# ODU_Display_Line_0603.net
KiCad netlist of a schematic drawn in EAGLE
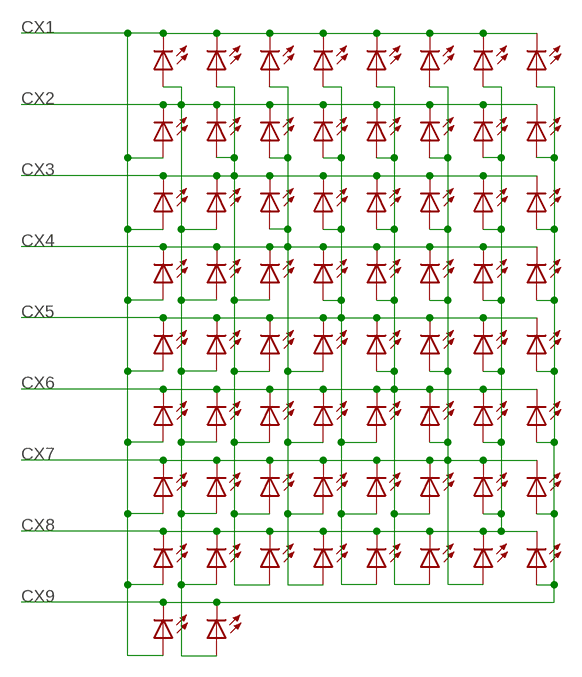
[diagram p0: schematic, sheet 1]

(export (version "E")
  (design (tool "Eeschema 10.0.6"))
  (components
    (comp (ref "LED_A1")
      (value "LEDSMT0603_1")
      (footprint "eagle-import:CHIPLED_0603")
      (libsource (lib "eagle-import") (part "LED0603_1SMT"))
    )
    (comp (ref "LED_A2")
      (value "LEDSMT0603_1")
      (footprint "eagle-import:CHIPLED_0603")
      (libsource (lib "eagle-import") (part "LED0603_1SMT"))
    )
    (comp (ref "LED_A3")
      (value "LEDSMT0603_1")
      (footprint "eagle-import:CHIPLED_0603")
      (libsource (lib "eagle-import") (part "LED0603_1SMT"))
    )
    (comp (ref "LED_A4")
      (value "LEDSMT0603_1")
      (footprint "eagle-import:CHIPLED_0603")
      (libsource (lib "eagle-import") (part "LED0603_1SMT"))
    )
    (comp (ref "LED_B1")
      (value "LEDSMT0603_1")
      (footprint "eagle-import:CHIPLED_0603")
      (libsource (lib "eagle-import") (part "LED0603_1SMT"))
    )
    (comp (ref "LED_B2")
      (value "LEDSMT0603_1")
      (footprint "eagle-import:CHIPLED_0603")
      (libsource (lib "eagle-import") (part "LED0603_1SMT"))
    )
    (comp (ref "LED_B3")
      (value "LEDSMT0603_1")
      (footprint "eagle-import:CHIPLED_0603")
      (libsource (lib "eagle-import") (part "LED0603_1SMT"))
    )
    (comp (ref "LED_B4")
      (value "LEDSMT0603_1")
      (footprint "eagle-import:CHIPLED_0603")
      (libsource (lib "eagle-import") (part "LED0603_1SMT"))
    )
    (comp (ref "LED_C1")
      (value "LEDSMT0603_1")
      (footprint "eagle-import:CHIPLED_0603")
      (libsource (lib "eagle-import") (part "LED0603_1SMT"))
    )
    (comp (ref "LED_C2")
      (value "LEDSMT0603_1")
      (footprint "eagle-import:CHIPLED_0603")
      (libsource (lib "eagle-import") (part "LED0603_1SMT"))
    )
    (comp (ref "LED_C3")
      (value "LEDSMT0603_1")
      (footprint "eagle-import:CHIPLED_0603")
      (libsource (lib "eagle-import") (part "LED0603_1SMT"))
    )
    (comp (ref "LED_C4")
      (value "LEDSMT0603_1")
      (footprint "eagle-import:CHIPLED_0603")
      (libsource (lib "eagle-import") (part "LED0603_1SMT"))
    )
    (comp (ref "LED_D1")
      (value "LEDSMT0603_1")
      (footprint "eagle-import:CHIPLED_0603")
      (libsource (lib "eagle-import") (part "LED0603_1SMT"))
    )
    (comp (ref "LED_D2")
      (value "LEDSMT0603_1")
      (footprint "eagle-import:CHIPLED_0603")
      (libsource (lib "eagle-import") (part "LED0603_1SMT"))
    )
    (comp (ref "LED_D3")
      (value "LEDSMT0603_1")
      (footprint "eagle-import:CHIPLED_0603")
      (libsource (lib "eagle-import") (part "LED0603_1SMT"))
    )
    (comp (ref "LED_D4")
      (value "LEDSMT0603_1")
      (footprint "eagle-import:CHIPLED_0603")
      (libsource (lib "eagle-import") (part "LED0603_1SMT"))
    )
    (comp (ref "LED_E1")
      (value "LEDSMT0603_1")
      (footprint "eagle-import:CHIPLED_0603")
      (libsource (lib "eagle-import") (part "LED0603_1SMT"))
    )
    (comp (ref "LED_E2")
      (value "LEDSMT0603_1")
      (footprint "eagle-import:CHIPLED_0603")
      (libsource (lib "eagle-import") (part "LED0603_1SMT"))
    )
    (comp (ref "LED_E3")
      (value "LEDSMT0603_1")
      (footprint "eagle-import:CHIPLED_0603")
      (libsource (lib "eagle-import") (part "LED0603_1SMT"))
    )
    (comp (ref "LED_E4")
      (value "LEDSMT0603_1")
      (footprint "eagle-import:CHIPLED_0603")
      (libsource (lib "eagle-import") (part "LED0603_1SMT"))
    )
    (comp (ref "LED_F1")
      (value "LEDSMT0603_1")
      (footprint "eagle-import:CHIPLED_0603")
      (libsource (lib "eagle-import") (part "LED0603_1SMT"))
    )
    (comp (ref "LED_F2")
      (value "LEDSMT0603_1")
      (footprint "eagle-import:CHIPLED_0603")
      (libsource (lib "eagle-import") (part "LED0603_1SMT"))
    )
    (comp (ref "LED_F3")
      (value "LEDSMT0603_1")
      (footprint "eagle-import:CHIPLED_0603")
      (libsource (lib "eagle-import") (part "LED0603_1SMT"))
    )
    (comp (ref "LED_F4")
      (value "LEDSMT0603_1")
      (footprint "eagle-import:CHIPLED_0603")
      (libsource (lib "eagle-import") (part "LED0603_1SMT"))
    )
    (comp (ref "LED_G1")
      (value "LEDSMT0603_1")
      (footprint "eagle-import:CHIPLED_0603")
      (libsource (lib "eagle-import") (part "LED0603_1SMT"))
    )
    (comp (ref "LED_G2")
      (value "LEDSMT0603_1")
      (footprint "eagle-import:CHIPLED_0603")
      (libsource (lib "eagle-import") (part "LED0603_1SMT"))
    )
    (comp (ref "LED_G3")
      (value "LEDSMT0603_1")
      (footprint "eagle-import:CHIPLED_0603")
      (libsource (lib "eagle-import") (part "LED0603_1SMT"))
    )
    (comp (ref "LED_G4")
      (value "LEDSMT0603_1")
      (footprint "eagle-import:CHIPLED_0603")
      (libsource (lib "eagle-import") (part "LED0603_1SMT"))
    )
    (comp (ref "LED_H1")
      (value "LEDSMT0603_1")
      (footprint "eagle-import:CHIPLED_0603")
      (libsource (lib "eagle-import") (part "LED0603_1SMT"))
    )
    (comp (ref "LED_H2")
      (value "LEDSMT0603_1")
      (footprint "eagle-import:CHIPLED_0603")
      (libsource (lib "eagle-import") (part "LED0603_1SMT"))
    )
    (comp (ref "LED_H3")
      (value "LEDSMT0603_1")
      (footprint "eagle-import:CHIPLED_0603")
      (libsource (lib "eagle-import") (part "LED0603_1SMT"))
    )
    (comp (ref "LED_H4")
      (value "LEDSMT0603_1")
      (footprint "eagle-import:CHIPLED_0603")
      (libsource (lib "eagle-import") (part "LED0603_1SMT"))
    )
    (comp (ref "LED_K1")
      (value "LEDSMT0603_1")
      (footprint "eagle-import:CHIPLED_0603")
      (libsource (lib "eagle-import") (part "LED0603_1SMT"))
    )
    (comp (ref "LED_K2")
      (value "LEDSMT0603_1")
      (footprint "eagle-import:CHIPLED_0603")
      (libsource (lib "eagle-import") (part "LED0603_1SMT"))
    )
    (comp (ref "LED_K3")
      (value "LEDSMT0603_1")
      (footprint "eagle-import:CHIPLED_0603")
      (libsource (lib "eagle-import") (part "LED0603_1SMT"))
    )
    (comp (ref "LED_K4")
      (value "LEDSMT0603_1")
      (footprint "eagle-import:CHIPLED_0603")
      (libsource (lib "eagle-import") (part "LED0603_1SMT"))
    )
    (comp (ref "LED_M1")
      (value "LEDSMT0603_1")
      (footprint "eagle-import:CHIPLED_0603")
      (libsource (lib "eagle-import") (part "LED0603_1SMT"))
    )
    (comp (ref "LED_M2")
      (value "LEDSMT0603_1")
      (footprint "eagle-import:CHIPLED_0603")
      (libsource (lib "eagle-import") (part "LED0603_1SMT"))
    )
    (comp (ref "LED_M3")
      (value "LEDSMT0603_1")
      (footprint "eagle-import:CHIPLED_0603")
      (libsource (lib "eagle-import") (part "LED0603_1SMT"))
    )
    (comp (ref "LED_M4")
      (value "LEDSMT0603_1")
      (footprint "eagle-import:CHIPLED_0603")
      (libsource (lib "eagle-import") (part "LED0603_1SMT"))
    )
    (comp (ref "LED_N1")
      (value "LEDSMT0603_1")
      (footprint "eagle-import:CHIPLED_0603")
      (libsource (lib "eagle-import") (part "LED0603_1SMT"))
    )
    (comp (ref "LED_N2")
      (value "LEDSMT0603_1")
      (footprint "eagle-import:CHIPLED_0603")
      (libsource (lib "eagle-import") (part "LED0603_1SMT"))
    )
    (comp (ref "LED_N3")
      (value "LEDSMT0603_1")
      (footprint "eagle-import:CHIPLED_0603")
      (libsource (lib "eagle-import") (part "LED0603_1SMT"))
    )
    (comp (ref "LED_N4")
      (value "LEDSMT0603_1")
      (footprint "eagle-import:CHIPLED_0603")
      (libsource (lib "eagle-import") (part "LED0603_1SMT"))
    )
    (comp (ref "LED_P1")
      (value "LEDSMT0603_1")
      (footprint "eagle-import:CHIPLED_0603")
      (libsource (lib "eagle-import") (part "LED0603_1SMT"))
    )
    (comp (ref "LED_P2")
      (value "LEDSMT0603_1")
      (footprint "eagle-import:CHIPLED_0603")
      (libsource (lib "eagle-import") (part "LED0603_1SMT"))
    )
    (comp (ref "LED_P3")
      (value "LEDSMT0603_1")
      (footprint "eagle-import:CHIPLED_0603")
      (libsource (lib "eagle-import") (part "LED0603_1SMT"))
    )
    (comp (ref "LED_P4")
      (value "LEDSMT0603_1")
      (footprint "eagle-import:CHIPLED_0603")
      (libsource (lib "eagle-import") (part "LED0603_1SMT"))
    )
    (comp (ref "LED_R1")
      (value "LEDSMT0603_1")
      (footprint "eagle-import:CHIPLED_0603")
      (libsource (lib "eagle-import") (part "LED0603_1SMT"))
    )
    (comp (ref "LED_R2")
      (value "LEDSMT0603_1")
      (footprint "eagle-import:CHIPLED_0603")
      (libsource (lib "eagle-import") (part "LED0603_1SMT"))
    )
    (comp (ref "LED_R3")
      (value "LEDSMT0603_1")
      (footprint "eagle-import:CHIPLED_0603")
      (libsource (lib "eagle-import") (part "LED0603_1SMT"))
    )
    (comp (ref "LED_R4")
      (value "LEDSMT0603_1")
      (footprint "eagle-import:CHIPLED_0603")
      (libsource (lib "eagle-import") (part "LED0603_1SMT"))
    )
    (comp (ref "LED_S1")
      (value "LEDSMT0603_1")
      (footprint "eagle-import:CHIPLED_0603")
      (libsource (lib "eagle-import") (part "LED0603_1SMT"))
    )
    (comp (ref "LED_S2")
      (value "LEDSMT0603_1")
      (footprint "eagle-import:CHIPLED_0603")
      (libsource (lib "eagle-import") (part "LED0603_1SMT"))
    )
    (comp (ref "LED_S3")
      (value "LEDSMT0603_1")
      (footprint "eagle-import:CHIPLED_0603")
      (libsource (lib "eagle-import") (part "LED0603_1SMT"))
    )
    (comp (ref "LED_S4")
      (value "LEDSMT0603_1")
      (footprint "eagle-import:CHIPLED_0603")
      (libsource (lib "eagle-import") (part "LED0603_1SMT"))
    )
    (comp (ref "LED_SEL1")
      (value "LEDSMT0603_1")
      (footprint "eagle-import:CHIPLED_0603")
      (libsource (lib "eagle-import") (part "LED0603_1SMT"))
    )
    (comp (ref "LED_SEL2")
      (value "LEDSMT0603_1")
      (footprint "eagle-import:CHIPLED_0603")
      (libsource (lib "eagle-import") (part "LED0603_1SMT"))
    )
    (comp (ref "LED_T1")
      (value "LEDSMT0603_1")
      (footprint "eagle-import:CHIPLED_0603")
      (libsource (lib "eagle-import") (part "LED0603_1SMT"))
    )
    (comp (ref "LED_T2")
      (value "LEDSMT0603_1")
      (footprint "eagle-import:CHIPLED_0603")
      (libsource (lib "eagle-import") (part "LED0603_1SMT"))
    )
    (comp (ref "LED_T3")
      (value "LEDSMT0603_1")
      (footprint "eagle-import:CHIPLED_0603")
      (libsource (lib "eagle-import") (part "LED0603_1SMT"))
    )
    (comp (ref "LED_T4")
      (value "LEDSMT0603_1")
      (footprint "eagle-import:CHIPLED_0603")
      (libsource (lib "eagle-import") (part "LED0603_1SMT"))
    )
    (comp (ref "LED_U1")
      (value "LEDSMT0603_1")
      (footprint "eagle-import:CHIPLED_0603")
      (libsource (lib "eagle-import") (part "LED0603_1SMT"))
    )
    (comp (ref "LED_U2")
      (value "LEDSMT0603_1")
      (footprint "eagle-import:CHIPLED_0603")
      (libsource (lib "eagle-import") (part "LED0603_1SMT"))
    )
    (comp (ref "LED_U3")
      (value "LEDSMT0603_1")
      (footprint "eagle-import:CHIPLED_0603")
      (libsource (lib "eagle-import") (part "LED0603_1SMT"))
    )
    (comp (ref "LED_U4")
      (value "LEDSMT0603_1")
      (footprint "eagle-import:CHIPLED_0603")
      (libsource (lib "eagle-import") (part "LED0603_1SMT"))
    )
  )
  (nets
    (net (code "1") (name "/CX1") (class "Default")
      (node (ref "LED_A1") (pin "C") (pinfunction "C_C") (pintype "passive"))
      (node (ref "LED_A2") (pin "A") (pinfunction "A_A") (pintype "passive"))
      (node (ref "LED_A3") (pin "A") (pinfunction "A_A") (pintype "passive"))
      (node (ref "LED_A4") (pin "A") (pinfunction "A_A") (pintype "passive"))
      (node (ref "LED_B1") (pin "C") (pinfunction "C_C") (pintype "passive"))
      (node (ref "LED_C1") (pin "C") (pinfunction "C_C") (pintype "passive"))
      (node (ref "LED_D1") (pin "C") (pinfunction "C_C") (pintype "passive"))
      (node (ref "LED_E1") (pin "C") (pinfunction "C_C") (pintype "passive"))
      (node (ref "LED_F1") (pin "C") (pinfunction "C_C") (pintype "passive"))
      (node (ref "LED_G1") (pin "C") (pinfunction "C_C") (pintype "passive"))
      (node (ref "LED_H1") (pin "C") (pinfunction "C_C") (pintype "passive"))
      (node (ref "LED_K1") (pin "A") (pinfunction "A_A") (pintype "passive"))
      (node (ref "LED_K2") (pin "A") (pinfunction "A_A") (pintype "passive"))
      (node (ref "LED_K3") (pin "A") (pinfunction "A_A") (pintype "passive"))
      (node (ref "LED_K4") (pin "A") (pinfunction "A_A") (pintype "passive"))
      (node (ref "LED_SEL1") (pin "A") (pinfunction "A_A") (pintype "passive"))
    )
    (net (code "2") (name "/CX2") (class "Default")
      (node (ref "LED_A1") (pin "A") (pinfunction "A_A") (pintype "passive"))
      (node (ref "LED_B2") (pin "A") (pinfunction "A_A") (pintype "passive"))
      (node (ref "LED_B3") (pin "A") (pinfunction "A_A") (pintype "passive"))
      (node (ref "LED_B4") (pin "A") (pinfunction "A_A") (pintype "passive"))
      (node (ref "LED_K1") (pin "C") (pinfunction "C_C") (pintype "passive"))
      (node (ref "LED_M1") (pin "C") (pinfunction "C_C") (pintype "passive"))
      (node (ref "LED_M2") (pin "A") (pinfunction "A_A") (pintype "passive"))
      (node (ref "LED_M3") (pin "A") (pinfunction "A_A") (pintype "passive"))
      (node (ref "LED_M4") (pin "A") (pinfunction "A_A") (pintype "passive"))
      (node (ref "LED_N1") (pin "C") (pinfunction "C_C") (pintype "passive"))
      (node (ref "LED_P1") (pin "C") (pinfunction "C_C") (pintype "passive"))
      (node (ref "LED_R1") (pin "C") (pinfunction "C_C") (pintype "passive"))
      (node (ref "LED_S1") (pin "C") (pinfunction "C_C") (pintype "passive"))
      (node (ref "LED_SEL2") (pin "A") (pinfunction "A_A") (pintype "passive"))
      (node (ref "LED_T1") (pin "C") (pinfunction "C_C") (pintype "passive"))
      (node (ref "LED_U1") (pin "C") (pinfunction "C_C") (pintype "passive"))
    )
    (net (code "3") (name "/CX3") (class "Default")
      (node (ref "LED_A2") (pin "C") (pinfunction "C_C") (pintype "passive"))
      (node (ref "LED_B1") (pin "A") (pinfunction "A_A") (pintype "passive"))
      (node (ref "LED_B2") (pin "C") (pinfunction "C_C") (pintype "passive"))
      (node (ref "LED_C2") (pin "C") (pinfunction "C_C") (pintype "passive"))
      (node (ref "LED_C3") (pin "A") (pinfunction "A_A") (pintype "passive"))
      (node (ref "LED_C4") (pin "A") (pinfunction "A_A") (pintype "passive"))
      (node (ref "LED_D2") (pin "C") (pinfunction "C_C") (pintype "passive"))
      (node (ref "LED_E2") (pin "C") (pinfunction "C_C") (pintype "passive"))
      (node (ref "LED_F2") (pin "C") (pinfunction "C_C") (pintype "passive"))
      (node (ref "LED_G2") (pin "C") (pinfunction "C_C") (pintype "passive"))
      (node (ref "LED_H2") (pin "C") (pinfunction "C_C") (pintype "passive"))
      (node (ref "LED_M1") (pin "A") (pinfunction "A_A") (pintype "passive"))
      (node (ref "LED_N2") (pin "A") (pinfunction "A_A") (pintype "passive"))
      (node (ref "LED_N3") (pin "A") (pinfunction "A_A") (pintype "passive"))
      (node (ref "LED_N4") (pin "A") (pinfunction "A_A") (pintype "passive"))
    )
    (net (code "4") (name "/CX4") (class "Default")
      (node (ref "LED_C1") (pin "A") (pinfunction "A_A") (pintype "passive"))
      (node (ref "LED_C2") (pin "A") (pinfunction "A_A") (pintype "passive"))
      (node (ref "LED_D3") (pin "A") (pinfunction "A_A") (pintype "passive"))
      (node (ref "LED_D4") (pin "A") (pinfunction "A_A") (pintype "passive"))
      (node (ref "LED_K2") (pin "C") (pinfunction "C_C") (pintype "passive"))
      (node (ref "LED_M2") (pin "C") (pinfunction "C_C") (pintype "passive"))
      (node (ref "LED_N1") (pin "A") (pinfunction "A_A") (pintype "passive"))
      (node (ref "LED_N2") (pin "C") (pinfunction "C_C") (pintype "passive"))
      (node (ref "LED_P2") (pin "C") (pinfunction "C_C") (pintype "passive"))
      (node (ref "LED_P3") (pin "A") (pinfunction "A_A") (pintype "passive"))
      (node (ref "LED_P4") (pin "A") (pinfunction "A_A") (pintype "passive"))
      (node (ref "LED_R2") (pin "C") (pinfunction "C_C") (pintype "passive"))
      (node (ref "LED_S2") (pin "C") (pinfunction "C_C") (pintype "passive"))
      (node (ref "LED_T2") (pin "C") (pinfunction "C_C") (pintype "passive"))
      (node (ref "LED_U2") (pin "C") (pinfunction "C_C") (pintype "passive"))
    )
    (net (code "5") (name "/CX5") (class "Default")
      (node (ref "LED_A3") (pin "C") (pinfunction "C_C") (pintype "passive"))
      (node (ref "LED_B3") (pin "C") (pinfunction "C_C") (pintype "passive"))
      (node (ref "LED_C3") (pin "C") (pinfunction "C_C") (pintype "passive"))
      (node (ref "LED_D1") (pin "A") (pinfunction "A_A") (pintype "passive"))
      (node (ref "LED_D2") (pin "A") (pinfunction "A_A") (pintype "passive"))
      (node (ref "LED_D3") (pin "C") (pinfunction "C_C") (pintype "passive"))
      (node (ref "LED_E3") (pin "C") (pinfunction "C_C") (pintype "passive"))
      (node (ref "LED_E4") (pin "A") (pinfunction "A_A") (pintype "passive"))
      (node (ref "LED_F3") (pin "C") (pinfunction "C_C") (pintype "passive"))
      (node (ref "LED_G3") (pin "C") (pinfunction "C_C") (pintype "passive"))
      (node (ref "LED_H3") (pin "C") (pinfunction "C_C") (pintype "passive"))
      (node (ref "LED_P1") (pin "A") (pinfunction "A_A") (pintype "passive"))
      (node (ref "LED_P2") (pin "A") (pinfunction "A_A") (pintype "passive"))
      (node (ref "LED_R3") (pin "A") (pinfunction "A_A") (pintype "passive"))
      (node (ref "LED_R4") (pin "A") (pinfunction "A_A") (pintype "passive"))
    )
    (net (code "6") (name "/CX6") (class "Default")
      (node (ref "LED_E1") (pin "A") (pinfunction "A_A") (pintype "passive"))
      (node (ref "LED_E2") (pin "A") (pinfunction "A_A") (pintype "passive"))
      (node (ref "LED_E3") (pin "A") (pinfunction "A_A") (pintype "passive"))
      (node (ref "LED_F4") (pin "A") (pinfunction "A_A") (pintype "passive"))
      (node (ref "LED_K3") (pin "C") (pinfunction "C_C") (pintype "passive"))
      (node (ref "LED_M3") (pin "C") (pinfunction "C_C") (pintype "passive"))
      (node (ref "LED_N3") (pin "C") (pinfunction "C_C") (pintype "passive"))
      (node (ref "LED_P3") (pin "C") (pinfunction "C_C") (pintype "passive"))
      (node (ref "LED_R1") (pin "A") (pinfunction "A_A") (pintype "passive"))
      (node (ref "LED_R2") (pin "A") (pinfunction "A_A") (pintype "passive"))
      (node (ref "LED_R3") (pin "C") (pinfunction "C_C") (pintype "passive"))
      (node (ref "LED_S3") (pin "C") (pinfunction "C_C") (pintype "passive"))
      (node (ref "LED_S4") (pin "A") (pinfunction "A_A") (pintype "passive"))
      (node (ref "LED_T3") (pin "C") (pinfunction "C_C") (pintype "passive"))
      (node (ref "LED_U3") (pin "C") (pinfunction "C_C") (pintype "passive"))
    )
    (net (code "7") (name "/CX7") (class "Default")
      (node (ref "LED_A4") (pin "C") (pinfunction "C_C") (pintype "passive"))
      (node (ref "LED_B4") (pin "C") (pinfunction "C_C") (pintype "passive"))
      (node (ref "LED_C4") (pin "C") (pinfunction "C_C") (pintype "passive"))
      (node (ref "LED_D4") (pin "C") (pinfunction "C_C") (pintype "passive"))
      (node (ref "LED_E4") (pin "C") (pinfunction "C_C") (pintype "passive"))
      (node (ref "LED_F1") (pin "A") (pinfunction "A_A") (pintype "passive"))
      (node (ref "LED_F2") (pin "A") (pinfunction "A_A") (pintype "passive"))
      (node (ref "LED_F3") (pin "A") (pinfunction "A_A") (pintype "passive"))
      (node (ref "LED_F4") (pin "C") (pinfunction "C_C") (pintype "passive"))
      (node (ref "LED_G4") (pin "C") (pinfunction "C_C") (pintype "passive"))
      (node (ref "LED_H4") (pin "C") (pinfunction "C_C") (pintype "passive"))
      (node (ref "LED_S1") (pin "A") (pinfunction "A_A") (pintype "passive"))
      (node (ref "LED_S2") (pin "A") (pinfunction "A_A") (pintype "passive"))
      (node (ref "LED_S3") (pin "A") (pinfunction "A_A") (pintype "passive"))
      (node (ref "LED_T4") (pin "A") (pinfunction "A_A") (pintype "passive"))
    )
    (net (code "8") (name "/CX8") (class "Default")
      (node (ref "LED_G1") (pin "A") (pinfunction "A_A") (pintype "passive"))
      (node (ref "LED_G2") (pin "A") (pinfunction "A_A") (pintype "passive"))
      (node (ref "LED_G3") (pin "A") (pinfunction "A_A") (pintype "passive"))
      (node (ref "LED_G4") (pin "A") (pinfunction "A_A") (pintype "passive"))
      (node (ref "LED_K4") (pin "C") (pinfunction "C_C") (pintype "passive"))
      (node (ref "LED_M4") (pin "C") (pinfunction "C_C") (pintype "passive"))
      (node (ref "LED_N4") (pin "C") (pinfunction "C_C") (pintype "passive"))
      (node (ref "LED_P4") (pin "C") (pinfunction "C_C") (pintype "passive"))
      (node (ref "LED_R4") (pin "C") (pinfunction "C_C") (pintype "passive"))
      (node (ref "LED_S4") (pin "C") (pinfunction "C_C") (pintype "passive"))
      (node (ref "LED_T1") (pin "A") (pinfunction "A_A") (pintype "passive"))
      (node (ref "LED_T2") (pin "A") (pinfunction "A_A") (pintype "passive"))
      (node (ref "LED_T3") (pin "A") (pinfunction "A_A") (pintype "passive"))
      (node (ref "LED_T4") (pin "C") (pinfunction "C_C") (pintype "passive"))
      (node (ref "LED_U4") (pin "C") (pinfunction "C_C") (pintype "passive"))
    )
    (net (code "9") (name "/CX9") (class "Default")
      (node (ref "LED_H1") (pin "A") (pinfunction "A_A") (pintype "passive"))
      (node (ref "LED_H2") (pin "A") (pinfunction "A_A") (pintype "passive"))
      (node (ref "LED_H3") (pin "A") (pinfunction "A_A") (pintype "passive"))
      (node (ref "LED_H4") (pin "A") (pinfunction "A_A") (pintype "passive"))
      (node (ref "LED_SEL1") (pin "C") (pinfunction "C_C") (pintype "passive"))
      (node (ref "LED_SEL2") (pin "C") (pinfunction "C_C") (pintype "passive"))
      (node (ref "LED_U1") (pin "A") (pinfunction "A_A") (pintype "passive"))
      (node (ref "LED_U2") (pin "A") (pinfunction "A_A") (pintype "passive"))
      (node (ref "LED_U3") (pin "A") (pinfunction "A_A") (pintype "passive"))
      (node (ref "LED_U4") (pin "A") (pinfunction "A_A") (pintype "passive"))
    )
  )
)
